# EPS_3V3_Buck-Converter.net
KiCad netlist of a schematic drawn in Altium Designer
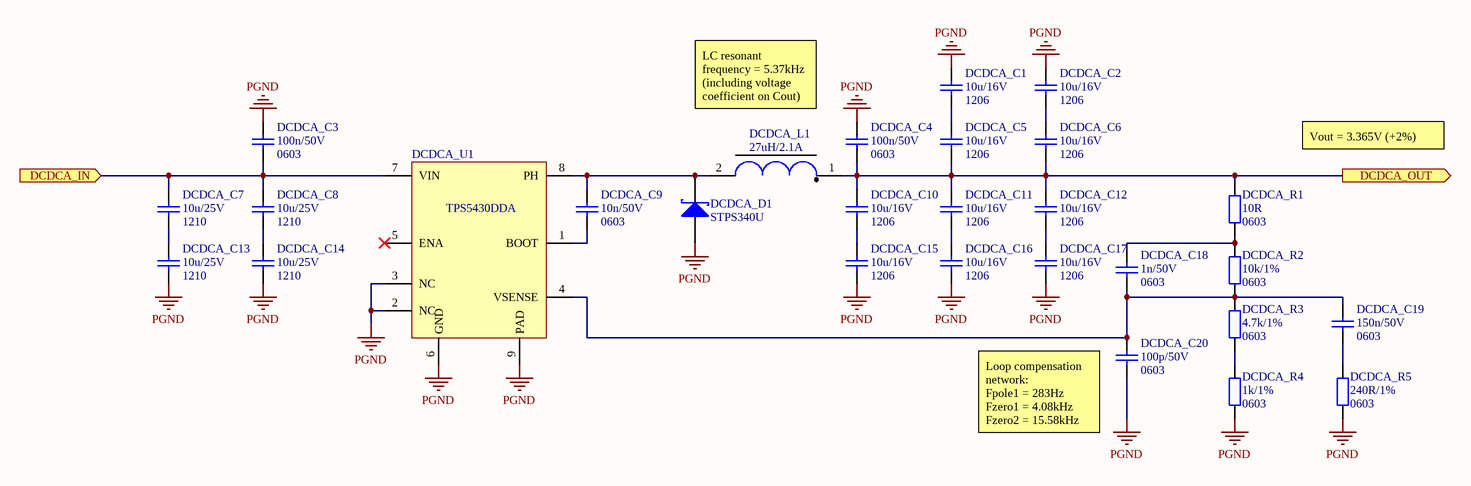
[diagram p0: EPS_3V3_Buck-Converter.SchDoc]

(export (version "E")
  (design (tool "Eeschema 10.0.6"))
  (components
    (comp (ref "DCDCA_C1")
      (value "10u/16V")
      (footprint "SMD_Capacitor_1206")
      (description "Ceramic Cap Kemet COTS 10u/16V X7R 1206")
      (fields
        (field (name "MANUFACTURERPARTNUMBER") "C1206T106K4RACTU")
        (field (name "MANUFACTURER") "Kemet")
        (field (name "PACKGE") "1206")
      )
      (libsource (lib "capacitors") (part "Cer_C1206T106K4RACTU"))
    )
    (comp (ref "DCDCA_C2")
      (value "10u/16V")
      (footprint "SMD_Capacitor_1206")
      (description "Ceramic Cap Kemet COTS 10u/16V X7R 1206")
      (fields
        (field (name "MANUFACTURERPARTNUMBER") "C1206T106K4RACTU")
        (field (name "MANUFACTURER") "Kemet")
        (field (name "PACKGE") "1206")
      )
      (libsource (lib "capacitors") (part "Cer_C1206T106K4RACTU"))
    )
    (comp (ref "DCDCA_C3")
      (value "100n/50V")
      (footprint "SMD_Capacitor_0603")
      (description "Ceramic Cap Murata Automotive 100n/50V X7R 0603")
      (fields
        (field (name "MANUFACTURER") "Murata")
        (field (name "MANUFACTURERPARTNUMBER") "GCJ188R71H104KA12D")
        (field (name "PACKAGE") "0603")
      )
      (libsource (lib "capacitors") (part "Cer_GCJ188R71H104KA12D"))
    )
    (comp (ref "DCDCA_C4")
      (value "100n/50V")
      (footprint "SMD_Capacitor_0603")
      (description "Ceramic Cap Murata Automotive 100n/50V X7R 0603")
      (fields
        (field (name "MANUFACTURER") "Murata")
        (field (name "MANUFACTURERPARTNUMBER") "GCJ188R71H104KA12D")
        (field (name "PACKAGE") "0603")
      )
      (libsource (lib "capacitors") (part "Cer_GCJ188R71H104KA12D"))
    )
    (comp (ref "DCDCA_C5")
      (value "10u/16V")
      (footprint "SMD_Capacitor_1206")
      (description "Ceramic Cap Kemet COTS 10u/16V X7R 1206")
      (fields
        (field (name "MANUFACTURERPARTNUMBER") "C1206T106K4RACTU")
        (field (name "MANUFACTURER") "Kemet")
        (field (name "PACKGE") "1206")
      )
      (libsource (lib "capacitors") (part "Cer_C1206T106K4RACTU"))
    )
    (comp (ref "DCDCA_C6")
      (value "10u/16V")
      (footprint "SMD_Capacitor_1206")
      (description "Ceramic Cap Kemet COTS 10u/16V X7R 1206")
      (fields
        (field (name "MANUFACTURERPARTNUMBER") "C1206T106K4RACTU")
        (field (name "MANUFACTURER") "Kemet")
        (field (name "PACKGE") "1206")
      )
      (libsource (lib "capacitors") (part "Cer_C1206T106K4RACTU"))
    )
    (comp (ref "DCDCA_C7")
      (value "10u/25V")
      (footprint "SMD_Capacitor_1210")
      (description "Ceramic Cap Murata Automotive 10u/25V X7R 1210")
      (fields
        (field (name "MANUFACTURER") "Murata")
        (field (name "MANUFACTURERPARTNUMBER") "GCJ32ER71E106KA12L")
        (field (name "PACKAGE") "1210")
      )
      (libsource (lib "capacitors") (part "Cer_GCJ32ER71E106KA12L"))
    )
    (comp (ref "DCDCA_C8")
      (value "10u/25V")
      (footprint "SMD_Capacitor_1210")
      (description "Ceramic Cap Murata Automotive 10u/25V X7R 1210")
      (fields
        (field (name "MANUFACTURER") "Murata")
        (field (name "MANUFACTURERPARTNUMBER") "GCJ32ER71E106KA12L")
        (field (name "PACKAGE") "1210")
      )
      (libsource (lib "capacitors") (part "Cer_GCJ32ER71E106KA12L"))
    )
    (comp (ref "DCDCA_C9")
      (value "10n/50V")
      (footprint "SMD_Capacitor_0603")
      (description "Cap")
      (fields (field (name "PACKAGE") "0603"))
      (libsource (lib "capacitors") (part "Cap"))
    )
    (comp (ref "DCDCA_C10")
      (value "10u/16V")
      (footprint "SMD_Capacitor_1206")
      (description "Ceramic Cap Kemet COTS 10u/16V X7R 1206")
      (fields
        (field (name "MANUFACTURERPARTNUMBER") "C1206T106K4RACTU")
        (field (name "MANUFACTURER") "Kemet")
        (field (name "PACKGE") "1206")
      )
      (libsource (lib "capacitors") (part "Cer_C1206T106K4RACTU"))
    )
    (comp (ref "DCDCA_C11")
      (value "10u/16V")
      (footprint "SMD_Capacitor_1206")
      (description "Ceramic Cap Kemet COTS 10u/16V X7R 1206")
      (fields
        (field (name "MANUFACTURERPARTNUMBER") "C1206T106K4RACTU")
        (field (name "MANUFACTURER") "Kemet")
        (field (name "PACKGE") "1206")
      )
      (libsource (lib "capacitors") (part "Cer_C1206T106K4RACTU"))
    )
    (comp (ref "DCDCA_C12")
      (value "10u/16V")
      (footprint "SMD_Capacitor_1206")
      (description "Ceramic Cap Kemet COTS 10u/16V X7R 1206")
      (fields
        (field (name "MANUFACTURERPARTNUMBER") "C1206T106K4RACTU")
        (field (name "MANUFACTURER") "Kemet")
        (field (name "PACKGE") "1206")
      )
      (libsource (lib "capacitors") (part "Cer_C1206T106K4RACTU"))
    )
    (comp (ref "DCDCA_C13")
      (value "10u/25V")
      (footprint "SMD_Capacitor_1210")
      (description "Ceramic Cap Murata Automotive 10u/25V X7R 1210")
      (fields
        (field (name "MANUFACTURER") "Murata")
        (field (name "MANUFACTURERPARTNUMBER") "GCJ32ER71E106KA12L")
        (field (name "PACKAGE") "1210")
      )
      (libsource (lib "capacitors") (part "Cer_GCJ32ER71E106KA12L"))
    )
    (comp (ref "DCDCA_C14")
      (value "10u/25V")
      (footprint "SMD_Capacitor_1210")
      (description "Ceramic Cap Murata Automotive 10u/25V X7R 1210")
      (fields
        (field (name "MANUFACTURER") "Murata")
        (field (name "MANUFACTURERPARTNUMBER") "GCJ32ER71E106KA12L")
        (field (name "PACKAGE") "1210")
      )
      (libsource (lib "capacitors") (part "Cer_GCJ32ER71E106KA12L"))
    )
    (comp (ref "DCDCA_C15")
      (value "10u/16V")
      (footprint "SMD_Capacitor_1206")
      (description "Ceramic Cap Kemet COTS 10u/16V X7R 1206")
      (fields
        (field (name "MANUFACTURERPARTNUMBER") "C1206T106K4RACTU")
        (field (name "MANUFACTURER") "Kemet")
        (field (name "PACKGE") "1206")
      )
      (libsource (lib "capacitors") (part "Cer_C1206T106K4RACTU"))
    )
    (comp (ref "DCDCA_C16")
      (value "10u/16V")
      (footprint "SMD_Capacitor_1206")
      (description "Ceramic Cap Kemet COTS 10u/16V X7R 1206")
      (fields
        (field (name "MANUFACTURERPARTNUMBER") "C1206T106K4RACTU")
        (field (name "MANUFACTURER") "Kemet")
        (field (name "PACKGE") "1206")
      )
      (libsource (lib "capacitors") (part "Cer_C1206T106K4RACTU"))
    )
    (comp (ref "DCDCA_C17")
      (value "10u/16V")
      (footprint "SMD_Capacitor_1206")
      (description "Ceramic Cap Kemet COTS 10u/16V X7R 1206")
      (fields
        (field (name "MANUFACTURERPARTNUMBER") "C1206T106K4RACTU")
        (field (name "MANUFACTURER") "Kemet")
        (field (name "PACKGE") "1206")
      )
      (libsource (lib "capacitors") (part "Cer_C1206T106K4RACTU"))
    )
    (comp (ref "DCDCA_C18")
      (value "1n/50V")
      (footprint "SMD_Capacitor_0603")
      (description "Cap")
      (fields (field (name "PACKAGE") "0603"))
      (libsource (lib "capacitors") (part "Cap"))
    )
    (comp (ref "DCDCA_C19")
      (value "150n/50V")
      (footprint "SMD_Capacitor_0603")
      (description "Ceramic Cap Murata Automotive 150n/50V X7R 0603")
      (fields
        (field (name "MANUFACTURER") "Murata")
        (field (name "MANUFACTURERPARTNUMBER") "GCM188R71H154KA64D")
        (field (name "PACKAGE") "0603")
      )
      (libsource (lib "capacitors") (part "Cer_GCM188R71H154KA64D"))
    )
    (comp (ref "DCDCA_C20")
      (value "100p/50V")
      (footprint "SMD_Capacitor_0603")
      (description "Cap")
      (fields (field (name "PACKAGE") "0603"))
      (libsource (lib "capacitors") (part "Cap"))
    )
    (comp (ref "DCDCA_D1")
      (value "STPS340U")
      (footprint "DO-214AA")
      (description "3A/40V Power Schottky Rectifier.")
      (fields (field (name "MANUFACTURER") "STMicroelectronics"))
      (libsource (lib "diodes") (part "STPS340x"))
    )
    (comp (ref "DCDCA_L1")
      (value "27uH/2.1A")
      (footprint "Coilcraft_MSS1260")
      (description "Coilcraft MSS1260 Inductor, L=27uH, Irise20deg=2.1A, ESR=50mR, SRF=13MHz.")
      (fields
        (field (name "MANUFACTURER") "Coilcraft")
        (field (name "MANUFACTURERPARTNUMBER") "MSS1260-273MLx")
      )
      (libsource (lib "inductors") (part "MSS1260-273MLx"))
    )
    (comp (ref "DCDCA_R1")
      (value "10R")
      (footprint "SMD_Resistor_0603")
      (fields (field (name "PACKAGE") "0603"))
      (libsource (lib "resistors") (part "Res"))
    )
    (comp (ref "DCDCA_R2")
      (value "10k/1%")
      (footprint "SMD_Resistor_0603")
      (fields (field (name "PACKAGE") "0603"))
      (libsource (lib "resistors") (part "Res"))
    )
    (comp (ref "DCDCA_R3")
      (value "4.7k/1%")
      (footprint "SMD_Resistor_0603")
      (fields (field (name "PACKAGE") "0603"))
      (libsource (lib "resistors") (part "Res"))
    )
    (comp (ref "DCDCA_R4")
      (value "1k/1%")
      (footprint "SMD_Resistor_0603")
      (fields (field (name "PACKAGE") "0603"))
      (libsource (lib "resistors") (part "Res"))
    )
    (comp (ref "DCDCA_R5")
      (value "240R/1%")
      (footprint "SMD_Resistor_0603")
      (fields (field (name "PACKAGE") "0603"))
      (libsource (lib "resistors") (part "Res"))
    )
    (comp (ref "DCDCA_U1")
      (value "TPS5430DDA")
      (footprint "DDA-9")
      (description "TPS5430 3-A, Wide Input Range, Step-Down Converter")
      (fields (field (name "MANUFACTURER") "Texas Instruments"))
      (libsource (lib "microcircuits") (part "TPS5430"))
    )
  )
  (nets
    (net (code "1") (name "/DCDCA_IN") (class "Default")
      (node (ref "DCDCA_C3") (pin "1") (pinfunction "1_1") (pintype "passive"))
      (node (ref "DCDCA_C7") (pin "1") (pinfunction "1_1") (pintype "passive"))
      (node (ref "DCDCA_C8") (pin "1") (pinfunction "1_1") (pintype "passive"))
      (node (ref "DCDCA_U1") (pin "7") (pinfunction "VIN_7") (pintype "passive"))
    )
    (net (code "2") (name "/DCDCA_OUT") (class "Default")
      (node (ref "DCDCA_C10") (pin "1") (pinfunction "1_1") (pintype "passive"))
      (node (ref "DCDCA_C11") (pin "1") (pinfunction "1_1") (pintype "passive"))
      (node (ref "DCDCA_C12") (pin "1") (pinfunction "1_1") (pintype "passive"))
      (node (ref "DCDCA_C4") (pin "1") (pinfunction "1_1") (pintype "passive"))
      (node (ref "DCDCA_C5") (pin "2") (pinfunction "2_2") (pintype "passive"))
      (node (ref "DCDCA_C6") (pin "2") (pinfunction "2_2") (pintype "passive"))
      (node (ref "DCDCA_L1") (pin "1") (pinfunction "1_1") (pintype "passive"))
      (node (ref "DCDCA_R1") (pin "2") (pinfunction "2_2") (pintype "passive"))
    )
    (net (code "3") (name "Net-(DCDCA_C1-Pad2)") (class "Default")
      (node (ref "DCDCA_C1") (pin "2") (pinfunction "2_2") (pintype "passive"))
      (node (ref "DCDCA_C5") (pin "1") (pinfunction "1_1") (pintype "passive"))
    )
    (net (code "4") (name "Net-(DCDCA_C2-Pad2)") (class "Default")
      (node (ref "DCDCA_C2") (pin "2") (pinfunction "2_2") (pintype "passive"))
      (node (ref "DCDCA_C6") (pin "1") (pinfunction "1_1") (pintype "passive"))
    )
    (net (code "5") (name "Net-(DCDCA_C10-Pad2)") (class "Default")
      (node (ref "DCDCA_C10") (pin "2") (pinfunction "2_2") (pintype "passive"))
      (node (ref "DCDCA_C15") (pin "1") (pinfunction "1_1") (pintype "passive"))
    )
    (net (code "6") (name "Net-(DCDCA_C11-Pad2)") (class "Default")
      (node (ref "DCDCA_C11") (pin "2") (pinfunction "2_2") (pintype "passive"))
      (node (ref "DCDCA_C16") (pin "1") (pinfunction "1_1") (pintype "passive"))
    )
    (net (code "7") (name "Net-(DCDCA_C12-Pad2)") (class "Default")
      (node (ref "DCDCA_C12") (pin "2") (pinfunction "2_2") (pintype "passive"))
      (node (ref "DCDCA_C17") (pin "1") (pinfunction "1_1") (pintype "passive"))
    )
    (net (code "8") (name "Net-(DCDCA_C13-Pad1)") (class "Default")
      (node (ref "DCDCA_C13") (pin "1") (pinfunction "1_1") (pintype "passive"))
      (node (ref "DCDCA_C7") (pin "2") (pinfunction "2_2") (pintype "passive"))
    )
    (net (code "9") (name "Net-(DCDCA_C14-Pad1)") (class "Default")
      (node (ref "DCDCA_C14") (pin "1") (pinfunction "1_1") (pintype "passive"))
      (node (ref "DCDCA_C8") (pin "2") (pinfunction "2_2") (pintype "passive"))
    )
    (net (code "10") (name "Net-(DCDCA_C18-Pad1)") (class "Default")
      (node (ref "DCDCA_C18") (pin "1") (pinfunction "1_1") (pintype "passive"))
      (node (ref "DCDCA_R1") (pin "1") (pinfunction "1_1") (pintype "passive"))
      (node (ref "DCDCA_R2") (pin "2") (pinfunction "2_2") (pintype "passive"))
    )
    (net (code "11") (name "Net-(DCDCA_C19-Pad2)") (class "Default")
      (node (ref "DCDCA_C19") (pin "2") (pinfunction "2_2") (pintype "passive"))
      (node (ref "DCDCA_R5") (pin "2") (pinfunction "2_2") (pintype "passive"))
    )
    (net (code "12") (name "Net-(DCDCA_R3-Pad1)") (class "Default")
      (node (ref "DCDCA_R3") (pin "1") (pinfunction "1_1") (pintype "passive"))
      (node (ref "DCDCA_R4") (pin "2") (pinfunction "2_2") (pintype "passive"))
    )
    (net (code "13") (name "Net-(DCDCA_U1-BOOT)") (class "Default")
      (node (ref "DCDCA_C9") (pin "2") (pinfunction "2_2") (pintype "passive"))
      (node (ref "DCDCA_U1") (pin "1") (pinfunction "BOOT_1") (pintype "passive"))
    )
    (net (code "14") (name "Net-(DCDCA_U1-PH)") (class "Default")
      (node (ref "DCDCA_C9") (pin "1") (pinfunction "1_1") (pintype "passive"))
      (node (ref "DCDCA_D1") (pin "K") (pinfunction "K_K") (pintype "passive"))
      (node (ref "DCDCA_L1") (pin "2") (pinfunction "2_2") (pintype "passive"))
      (node (ref "DCDCA_U1") (pin "8") (pinfunction "PH_8") (pintype "passive"))
    )
    (net (code "15") (name "Net-(DCDCA_U1-VSENSE)") (class "Default")
      (node (ref "DCDCA_C18") (pin "2") (pinfunction "2_2") (pintype "passive"))
      (node (ref "DCDCA_C19") (pin "1") (pinfunction "1_1") (pintype "passive"))
      (node (ref "DCDCA_C20") (pin "1") (pinfunction "1_1") (pintype "passive"))
      (node (ref "DCDCA_R2") (pin "1") (pinfunction "1_1") (pintype "passive"))
      (node (ref "DCDCA_R3") (pin "2") (pinfunction "2_2") (pintype "passive"))
      (node (ref "DCDCA_U1") (pin "4") (pinfunction "VSENSE_4") (pintype "passive"))
    )
    (net (code "16") (name "PGND") (class "Default")
      (node (ref "DCDCA_C1") (pin "1") (pinfunction "1_1") (pintype "passive"))
      (node (ref "DCDCA_C13") (pin "2") (pinfunction "2_2") (pintype "passive"))
      (node (ref "DCDCA_C14") (pin "2") (pinfunction "2_2") (pintype "passive"))
      (node (ref "DCDCA_C15") (pin "2") (pinfunction "2_2") (pintype "passive"))
      (node (ref "DCDCA_C16") (pin "2") (pinfunction "2_2") (pintype "passive"))
      (node (ref "DCDCA_C17") (pin "2") (pinfunction "2_2") (pintype "passive"))
      (node (ref "DCDCA_C2") (pin "1") (pinfunction "1_1") (pintype "passive"))
      (node (ref "DCDCA_C20") (pin "2") (pinfunction "2_2") (pintype "passive"))
      (node (ref "DCDCA_C3") (pin "2") (pinfunction "2_2") (pintype "passive"))
      (node (ref "DCDCA_C4") (pin "2") (pinfunction "2_2") (pintype "passive"))
      (node (ref "DCDCA_D1") (pin "A") (pinfunction "A_A") (pintype "passive"))
      (node (ref "DCDCA_R4") (pin "1") (pinfunction "1_1") (pintype "passive"))
      (node (ref "DCDCA_R5") (pin "1") (pinfunction "1_1") (pintype "passive"))
      (node (ref "DCDCA_U1") (pin "2") (pinfunction "NC_2") (pintype "passive"))
      (node (ref "DCDCA_U1") (pin "3") (pinfunction "NC_3") (pintype "passive"))
      (node (ref "DCDCA_U1") (pin "6") (pinfunction "GND_6") (pintype "passive"))
      (node (ref "DCDCA_U1") (pin "9") (pinfunction "PAD_9") (pintype "passive"))
    )
    (net (code "17") (name "unconnected-(DCDCA_U1-ENA-Pad5)") (class "Default")
      (node (ref "DCDCA_U1") (pin "5") (pinfunction "ENA_5") (pintype "passive+no_connect"))
    )
  )
)
